# Sensor.net
KiCad netlist of a schematic drawn in Altium Designer
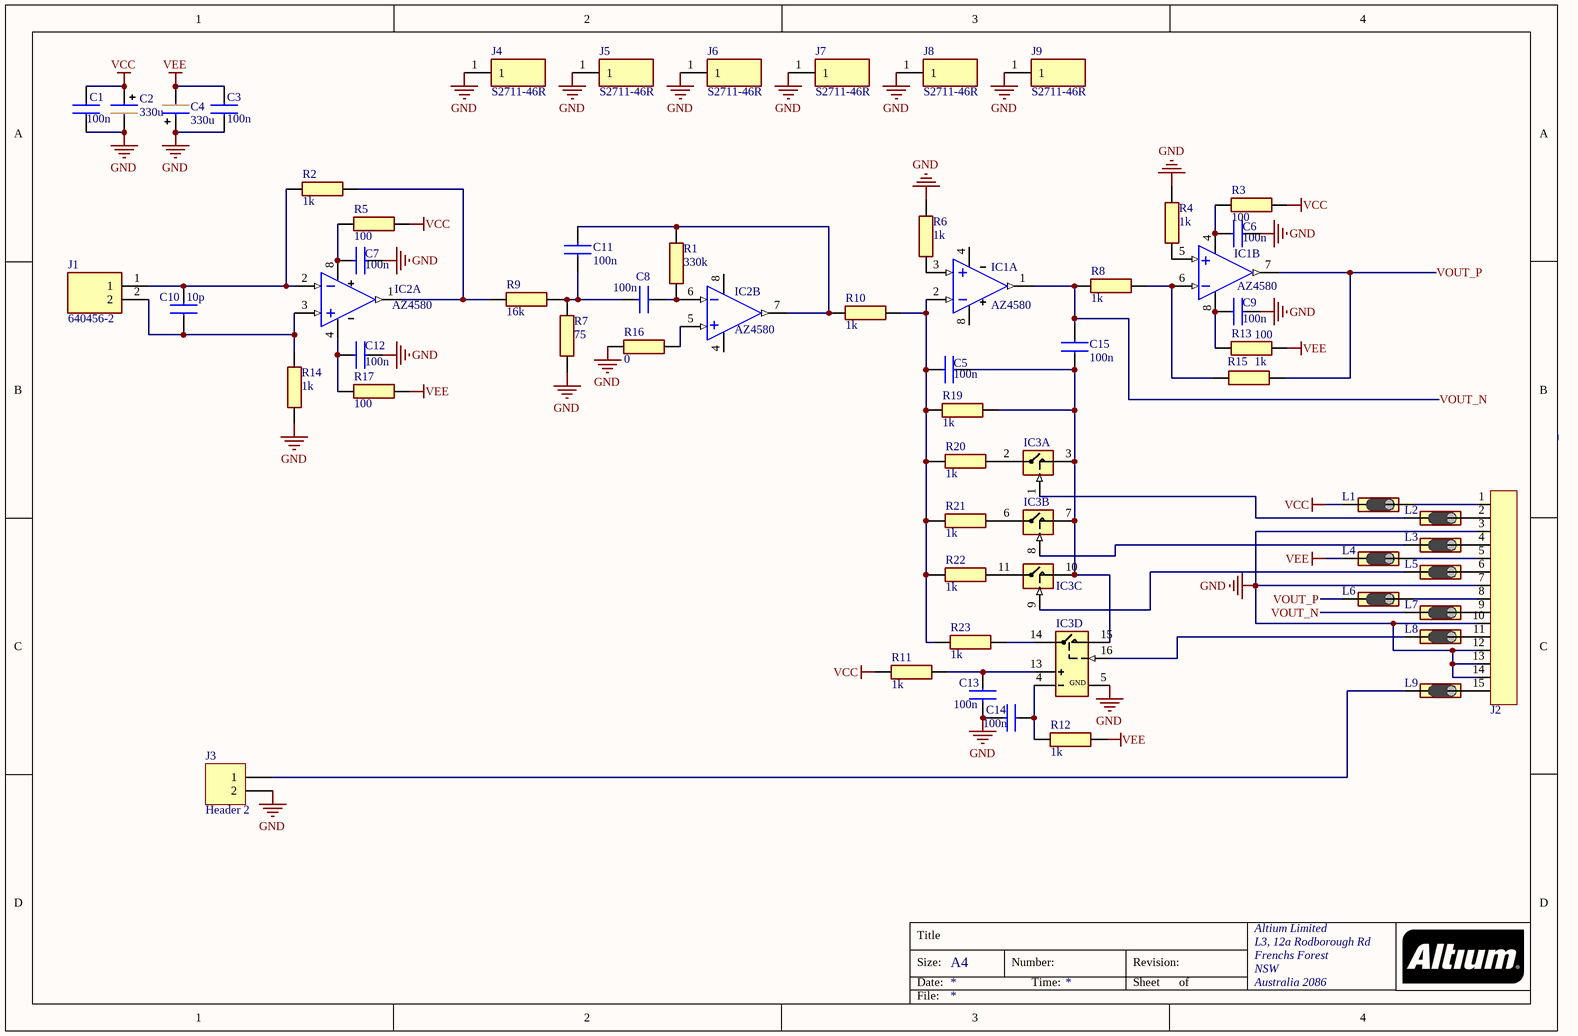
[diagram p0: Sensor.SchDoc]

(export (version "E")
  (design (tool "Eeschema 10.0.6"))
  (components
    (comp (ref "C1")
      (value "100n")
      (footprint "CAPC2012X140N")
      (description "Capacitor smd ceramic")
      (fields
        (field (name "MANUFACTURER_PART_NUMBER") "C3216C0G1H562J060AA")
        (field (name "Comment") "Capacitor_SMD")
      )
      (libsource (lib "Schlib") (part "Capacitor_SMD"))
    )
    (comp (ref "C2")
      (value "330u")
      (footprint "CAP_EL_8X12R3_5")
      (description "Capacitor polarized electrolytic")
      (fields
        (field (name "MANUFACTURER_PART_NUMBER") "B43640A9477M")
        (field (name "MOUSER PART NUMBER") "871-B43640A9477M")
      )
      (libsource (lib "Schlib") (part "Capacitor Electrolytic"))
    )
    (comp (ref "C3")
      (value "100n")
      (footprint "CAPC2012X140N")
      (description "Capacitor smd ceramic")
      (fields
        (field (name "MANUFACTURER_PART_NUMBER") "C3216C0G1H562J060AA")
        (field (name "Comment") "Capacitor_SMD")
      )
      (libsource (lib "Schlib") (part "Capacitor_SMD"))
    )
    (comp (ref "C4")
      (value "330u")
      (footprint "CAP_EL_8X12R3_5")
      (description "Capacitor polarized electrolytic")
      (fields
        (field (name "MANUFACTURER_PART_NUMBER") "B43640A9477M")
        (field (name "MOUSER PART NUMBER") "871-B43640A9477M")
      )
      (libsource (lib "Schlib") (part "Capacitor Electrolytic"))
    )
    (comp (ref "C5")
      (value "100n")
      (footprint "CAPC2012X140N")
      (description "Capacitor smd ceramic")
      (fields
        (field (name "MANUFACTURER_PART_NUMBER") "C3216C0G1H562J060AA")
        (field (name "Comment") "Capacitor_SMD")
      )
      (libsource (lib "Schlib") (part "Capacitor_SMD"))
    )
    (comp (ref "C6")
      (value "100n")
      (footprint "CAPC2012X140N")
      (description "Capacitor smd ceramic")
      (fields
        (field (name "MANUFACTURER_PART_NUMBER") "C3216C0G1H562J060AA")
        (field (name "Comment") "Capacitor_SMD")
      )
      (libsource (lib "Schlib") (part "Capacitor_SMD"))
    )
    (comp (ref "C7")
      (value "100n")
      (footprint "CAPC2012X140N")
      (description "Capacitor smd ceramic")
      (fields
        (field (name "MANUFACTURER_PART_NUMBER") "C3216C0G1H562J060AA")
        (field (name "Comment") "Capacitor_SMD")
      )
      (libsource (lib "Schlib") (part "Capacitor_SMD"))
    )
    (comp (ref "C8")
      (value "100n")
      (footprint "CAPC3216X95N")
      (description "Capacitor smd ceramic")
      (fields
        (field (name "MANUFACTURER_PART_NUMBER") "C3216C0G1H562J060AA")
        (field (name "Comment") "Capacitor_SMD")
      )
      (libsource (lib "Schlib") (part "Capacitor_SMD"))
    )
    (comp (ref "C9")
      (value "100n")
      (footprint "CAPC2012X140N")
      (description "Capacitor smd ceramic")
      (fields
        (field (name "MANUFACTURER_PART_NUMBER") "C3216C0G1H562J060AA")
        (field (name "Comment") "Capacitor_SMD")
      )
      (libsource (lib "Schlib") (part "Capacitor_SMD"))
    )
    (comp (ref "C10")
      (value "10p")
      (footprint "CAPC2012X140N")
      (description "Capacitor smd ceramic")
      (fields
        (field (name "MANUFACTURER_PART_NUMBER") "C3216C0G1H562J060AA")
        (field (name "Comment") "Capacitor_SMD")
      )
      (libsource (lib "Schlib") (part "Capacitor_SMD"))
    )
    (comp (ref "C11")
      (value "100n")
      (footprint "CAPC3216X95N")
      (description "Capacitor smd ceramic")
      (fields
        (field (name "MANUFACTURER_PART_NUMBER") "C3216C0G1H562J060AA")
        (field (name "Comment") "Capacitor_SMD")
      )
      (libsource (lib "Schlib") (part "Capacitor_SMD"))
    )
    (comp (ref "C12")
      (value "100n")
      (footprint "CAPC2012X140N")
      (description "Capacitor smd ceramic")
      (fields
        (field (name "MANUFACTURER_PART_NUMBER") "C3216C0G1H562J060AA")
        (field (name "Comment") "Capacitor_SMD")
      )
      (libsource (lib "Schlib") (part "Capacitor_SMD"))
    )
    (comp (ref "C13")
      (value "100n")
      (footprint "CAPC2012X140N")
      (description "Capacitor smd ceramic")
      (fields
        (field (name "MANUFACTURER_PART_NUMBER") "C3216C0G1H562J060AA")
        (field (name "Comment") "Capacitor_SMD")
      )
      (libsource (lib "Schlib") (part "Capacitor_SMD"))
    )
    (comp (ref "C14")
      (value "100n")
      (footprint "CAPC2012X140N")
      (description "Capacitor smd ceramic")
      (fields
        (field (name "MANUFACTURER_PART_NUMBER") "C3216C0G1H562J060AA")
        (field (name "Comment") "Capacitor_SMD")
      )
      (libsource (lib "Schlib") (part "Capacitor_SMD"))
    )
    (comp (ref "C15")
      (value "100n")
      (footprint "CAPC3216X95N")
      (description "Capacitor smd ceramic")
      (fields
        (field (name "MANUFACTURER_PART_NUMBER") "C3216C0G1H562J060AA")
        (field (name "Comment") "Capacitor_SMD")
      )
      (libsource (lib "Schlib") (part "Capacitor_SMD"))
    )
    (comp (ref "IC1")
      (value "AZ4580")
      (footprint "SOP65P490X110-8N")
      (description "Operational amplifier")
      (fields (field (name "ARROW PART NUMBER") "AZ4580"))
      (libsource (lib "Schlib") (part "AZ4580"))
    )
    (comp (ref "IC2")
      (value "AZ4580")
      (footprint "SOP65P490X110-8N")
      (description "Operational amplifier")
      (fields (field (name "ARROW PART NUMBER") "AZ4580"))
      (libsource (lib "Schlib") (part "AZ4580"))
    )
    (comp (ref "IC3")
      (value "DG442DY-E3")
      (footprint "PcbLib:SOIC127P600X175-16N")
      (description "Integrated Circuit")
      (fields (field (name "MOUSER PART NUMBER") "781-DG442DY-E3"))
      (libsource (lib "Schlib") (part "DG442DY-E3"))
    )
    (comp (ref "J1")
      (value "640456-2")
      (footprint "PcbLib:SHDR2W66P0X254_1X2_508X572X1041P")
      (description "Connector")
      (fields (field (name "MOUSER PART NUMBER") "571-6404562"))
      (libsource (lib "Schlib") (part "640456-2"))
    )
    (comp (ref "J2")
      (value "D-Sub 15 pin")
      (footprint "PcbLib:ICD15S13E4GV00LF")
      (description "Connector D sub 9 pin pcb angled 90")
      (fields
        (field (name "MANUFACTURER_PART_NUMBER") "ICD15S13E4GV00LF")
        (field (name "MOUSER PART NUMBER") "649-ICD15S13E4GV00LF")
      )
      (libsource (lib "Schlib") (part "D-Sub 15 pin"))
    )
    (comp (ref "J3")
      (value "Header 2")
      (footprint "HDR1X2")
      (description "Header, 2-Pin")
      (fields (field (name "PUBLISHER") "Altium Limited"))
      (libsource (lib "Miscellaneous Connectors") (part "Header 2"))
    )
    (comp (ref "J4")
      (value "S2711-46R")
      (footprint "PcbLib:S271146R")
      (description "Connector")
      (fields (field (name "MOUSER PART NUMBER") "855-S2711-46R"))
      (libsource (lib "Schlib") (part "S2711-46R"))
    )
    (comp (ref "J5")
      (value "S2711-46R")
      (footprint "PcbLib:S271146R")
      (description "Connector")
      (fields (field (name "MOUSER PART NUMBER") "855-S2711-46R"))
      (libsource (lib "Schlib") (part "S2711-46R"))
    )
    (comp (ref "J6")
      (value "S2711-46R")
      (footprint "PcbLib:S271146R")
      (description "Connector")
      (fields (field (name "MOUSER PART NUMBER") "855-S2711-46R"))
      (libsource (lib "Schlib") (part "S2711-46R"))
    )
    (comp (ref "J7")
      (value "S2711-46R")
      (footprint "PcbLib:S271146R")
      (description "Connector")
      (fields (field (name "MOUSER PART NUMBER") "855-S2711-46R"))
      (libsource (lib "Schlib") (part "S2711-46R"))
    )
    (comp (ref "J8")
      (value "S2711-46R")
      (footprint "PcbLib:S271146R")
      (description "Connector")
      (fields (field (name "MOUSER PART NUMBER") "855-S2711-46R"))
      (libsource (lib "Schlib") (part "S2711-46R"))
    )
    (comp (ref "J9")
      (value "S2711-46R")
      (footprint "PcbLib:S271146R")
      (description "Connector")
      (fields (field (name "MOUSER PART NUMBER") "855-S2711-46R"))
      (libsource (lib "Schlib") (part "S2711-46R"))
    )
    (comp (ref "L1")
      (value "Ferrite Bead")
      (footprint "RESC2012X60N")
      (description "Bead ferrite")
      (libsource (lib "Schlib") (part "Ferrite Bead"))
    )
    (comp (ref "L2")
      (value "Ferrite Bead")
      (footprint "RESC2012X60N")
      (description "Bead ferrite")
      (libsource (lib "Schlib") (part "Ferrite Bead"))
    )
    (comp (ref "L3")
      (value "Ferrite Bead")
      (footprint "RESC2012X60N")
      (description "Bead ferrite")
      (libsource (lib "Schlib") (part "Ferrite Bead"))
    )
    (comp (ref "L4")
      (value "Ferrite Bead")
      (footprint "RESC2012X60N")
      (description "Bead ferrite")
      (libsource (lib "Schlib") (part "Ferrite Bead"))
    )
    (comp (ref "L5")
      (value "Ferrite Bead")
      (footprint "RESC2012X60N")
      (description "Bead ferrite")
      (libsource (lib "Schlib") (part "Ferrite Bead"))
    )
    (comp (ref "L6")
      (value "Ferrite Bead")
      (footprint "RESC2012X60N")
      (description "Bead ferrite")
      (libsource (lib "Schlib") (part "Ferrite Bead"))
    )
    (comp (ref "L7")
      (value "Ferrite Bead")
      (footprint "RESC2012X60N")
      (description "Bead ferrite")
      (libsource (lib "Schlib") (part "Ferrite Bead"))
    )
    (comp (ref "L8")
      (value "Ferrite Bead")
      (footprint "RESC2012X60N")
      (description "Bead ferrite")
      (libsource (lib "Schlib") (part "Ferrite Bead"))
    )
    (comp (ref "L9")
      (value "Ferrite Bead")
      (footprint "RESC2012X60N")
      (description "Bead ferrite")
      (libsource (lib "Schlib") (part "Ferrite Bead"))
    )
    (comp (ref "R1")
      (value "330k")
      (footprint "RESC2012X60N")
      (description "Resistor SMD")
      (fields
        (field (name "MANUFACTURER_PART_NUMBER") "CR1206-FW-1504ELF")
        (field (name "MOUSER PART NUMBER") "652-CR1206FW1504ELF")
      )
      (libsource (lib "Schlib") (part "Res_SMD"))
    )
    (comp (ref "R2")
      (value "1k")
      (footprint "RESC2012X60N")
      (description "Resistor SMD")
      (fields
        (field (name "MANUFACTURER_PART_NUMBER") "CR1206-FW-1504ELF")
        (field (name "MOUSER PART NUMBER") "652-CR1206FW1504ELF")
      )
      (libsource (lib "") (part "Res_SMD_2"))
    )
    (comp (ref "R3")
      (value "100")
      (footprint "RESC2012X60N")
      (description "Resistor SMD")
      (fields
        (field (name "MANUFACTURER_PART_NUMBER") "CR1206-FW-1504ELF")
        (field (name "MOUSER PART NUMBER") "652-CR1206FW1504ELF")
      )
      (libsource (lib "") (part "Res_SMD_1"))
    )
    (comp (ref "R4")
      (value "1k")
      (footprint "RESC2012X60N")
      (description "Resistor SMD")
      (fields
        (field (name "MANUFACTURER_PART_NUMBER") "CR1206-FW-1504ELF")
        (field (name "MOUSER PART NUMBER") "652-CR1206FW1504ELF")
      )
      (libsource (lib "") (part "Res_SMD_1"))
    )
    (comp (ref "R5")
      (value "100")
      (footprint "RESC2012X60N")
      (description "Resistor SMD")
      (fields
        (field (name "MANUFACTURER_PART_NUMBER") "CR1206-FW-1504ELF")
        (field (name "MOUSER PART NUMBER") "652-CR1206FW1504ELF")
      )
      (libsource (lib "") (part "Res_SMD_1"))
    )
    (comp (ref "R6")
      (value "1k")
      (footprint "RESC2012X60N")
      (description "Resistor SMD")
      (fields
        (field (name "MANUFACTURER_PART_NUMBER") "CR1206-FW-1504ELF")
        (field (name "MOUSER PART NUMBER") "652-CR1206FW1504ELF")
      )
      (libsource (lib "") (part "Res_SMD_1"))
    )
    (comp (ref "R7")
      (value "75")
      (footprint "RESC2012X60N")
      (description "Resistor SMD")
      (fields
        (field (name "MANUFACTURER_PART_NUMBER") "CR1206-FW-1504ELF")
        (field (name "MOUSER PART NUMBER") "652-CR1206FW1504ELF")
      )
      (libsource (lib "Schlib") (part "Res_SMD"))
    )
    (comp (ref "R8")
      (value "1k")
      (footprint "RESC2012X60N")
      (description "Resistor SMD")
      (fields
        (field (name "MANUFACTURER_PART_NUMBER") "CR1206-FW-1504ELF")
        (field (name "MOUSER PART NUMBER") "652-CR1206FW1504ELF")
      )
      (libsource (lib "") (part "Res_SMD_1"))
    )
    (comp (ref "R9")
      (value "16k")
      (footprint "RESC2012X60N")
      (description "Resistor SMD")
      (fields
        (field (name "MANUFACTURER_PART_NUMBER") "CR1206-FW-1504ELF")
        (field (name "MOUSER PART NUMBER") "652-CR1206FW1504ELF")
      )
      (libsource (lib "") (part "Res_SMD_2"))
    )
    (comp (ref "R10")
      (value "1k")
      (footprint "RESC2012X60N")
      (description "Resistor SMD")
      (fields
        (field (name "MANUFACTURER_PART_NUMBER") "CR1206-FW-1504ELF")
        (field (name "MOUSER PART NUMBER") "652-CR1206FW1504ELF")
      )
      (libsource (lib "") (part "Res_SMD_2"))
    )
    (comp (ref "R11")
      (value "1k")
      (footprint "RESC2012X60N")
      (description "Resistor SMD")
      (fields
        (field (name "MANUFACTURER_PART_NUMBER") "CR1206-FW-1504ELF")
        (field (name "MOUSER PART NUMBER") "652-CR1206FW1504ELF")
      )
      (libsource (lib "Schlib") (part "Res_SMD"))
    )
    (comp (ref "R12")
      (value "1k")
      (footprint "RESC2012X60N")
      (description "Resistor SMD")
      (fields
        (field (name "MANUFACTURER_PART_NUMBER") "CR1206-FW-1504ELF")
        (field (name "MOUSER PART NUMBER") "652-CR1206FW1504ELF")
      )
      (libsource (lib "Schlib") (part "Res_SMD"))
    )
    (comp (ref "R13")
      (value "100")
      (footprint "RESC2012X60N")
      (description "Resistor SMD")
      (fields
        (field (name "MANUFACTURER_PART_NUMBER") "CR1206-FW-1504ELF")
        (field (name "MOUSER PART NUMBER") "652-CR1206FW1504ELF")
      )
      (libsource (lib "") (part "Res_SMD_1"))
    )
    (comp (ref "R14")
      (value "1k")
      (footprint "RESC2012X60N")
      (description "Resistor SMD")
      (fields
        (field (name "MANUFACTURER_PART_NUMBER") "CR1206-FW-1504ELF")
        (field (name "MOUSER PART NUMBER") "652-CR1206FW1504ELF")
      )
      (libsource (lib "Schlib") (part "Res_SMD"))
    )
    (comp (ref "R15")
      (value "1k")
      (footprint "RESC2012X60N")
      (description "Resistor SMD")
      (fields
        (field (name "MANUFACTURER_PART_NUMBER") "CR1206-FW-1504ELF")
        (field (name "MOUSER PART NUMBER") "652-CR1206FW1504ELF")
      )
      (libsource (lib "") (part "Res_SMD_1"))
    )
    (comp (ref "R16")
      (value "0")
      (footprint "RESC2012X60N")
      (description "Resistor SMD")
      (fields
        (field (name "MANUFACTURER_PART_NUMBER") "CR1206-FW-1504ELF")
        (field (name "MOUSER PART NUMBER") "652-CR1206FW1504ELF")
      )
      (libsource (lib "") (part "Res_SMD_2"))
    )
    (comp (ref "R17")
      (value "100")
      (footprint "RESC2012X60N")
      (description "Resistor SMD")
      (fields
        (field (name "MANUFACTURER_PART_NUMBER") "CR1206-FW-1504ELF")
        (field (name "MOUSER PART NUMBER") "652-CR1206FW1504ELF")
      )
      (libsource (lib "") (part "Res_SMD_1"))
    )
    (comp (ref "R19")
      (value "1k")
      (footprint "RESC2012X60N")
      (description "Resistor SMD")
      (fields
        (field (name "MANUFACTURER_PART_NUMBER") "CR1206-FW-1504ELF")
        (field (name "MOUSER PART NUMBER") "652-CR1206FW1504ELF")
      )
      (libsource (lib "") (part "Res_SMD_2"))
    )
    (comp (ref "R20")
      (value "1k")
      (footprint "RESC2012X60N")
      (description "Resistor SMD")
      (fields
        (field (name "MANUFACTURER_PART_NUMBER") "CR1206-FW-1504ELF")
        (field (name "MOUSER PART NUMBER") "652-CR1206FW1504ELF")
      )
      (libsource (lib "Schlib") (part "Res_SMD"))
    )
    (comp (ref "R21")
      (value "1k")
      (footprint "RESC2012X60N")
      (description "Resistor SMD")
      (fields
        (field (name "MANUFACTURER_PART_NUMBER") "CR1206-FW-1504ELF")
        (field (name "MOUSER PART NUMBER") "652-CR1206FW1504ELF")
      )
      (libsource (lib "Schlib") (part "Res_SMD"))
    )
    (comp (ref "R22")
      (value "1k")
      (footprint "RESC2012X60N")
      (description "Resistor SMD")
      (fields
        (field (name "MANUFACTURER_PART_NUMBER") "CR1206-FW-1504ELF")
        (field (name "MOUSER PART NUMBER") "652-CR1206FW1504ELF")
      )
      (libsource (lib "Schlib") (part "Res_SMD"))
    )
    (comp (ref "R23")
      (value "1k")
      (footprint "RESC2012X60N")
      (description "Resistor SMD")
      (fields
        (field (name "MANUFACTURER_PART_NUMBER") "CR1206-FW-1504ELF")
        (field (name "MOUSER PART NUMBER") "652-CR1206FW1504ELF")
      )
      (libsource (lib "Schlib") (part "Res_SMD"))
    )
  )
  (nets
    (net (code "1") (name "/VOUT_N") (class "Default")
      (node (ref "C15") (pin "1") (pinfunction "1_1") (pintype "passive"))
      (node (ref "IC1") (pin "1") (pinfunction "OUT_1") (pintype "output"))
      (node (ref "L7") (pin "1") (pinfunction "1_1") (pintype "passive"))
      (node (ref "R8") (pin "2") (pinfunction "2_2") (pintype "passive"))
    )
    (net (code "2") (name "/VOUT_P") (class "Default")
      (node (ref "IC1") (pin "7") (pinfunction "OUT_7") (pintype "output"))
      (node (ref "L6") (pin "1") (pinfunction "1_1") (pintype "passive"))
      (node (ref "R15") (pin "1") (pinfunction "1_1") (pintype "passive"))
    )
    (net (code "3") (name "GND") (class "Default")
      (node (ref "C1") (pin "2") (pinfunction "2_2") (pintype "passive"))
      (node (ref "C12") (pin "1") (pinfunction "1_1") (pintype "passive"))
      (node (ref "C13") (pin "2") (pinfunction "2_2") (pintype "passive"))
      (node (ref "C14") (pin "1") (pinfunction "1_1") (pintype "passive"))
      (node (ref "C2") (pin "2") (pinfunction "-_2") (pintype "passive"))
      (node (ref "C3") (pin "2") (pinfunction "2_2") (pintype "passive"))
      (node (ref "C4") (pin "1") (pinfunction "+_1") (pintype "passive"))
      (node (ref "C6") (pin "1") (pinfunction "1_1") (pintype "passive"))
      (node (ref "C7") (pin "1") (pinfunction "1_1") (pintype "passive"))
      (node (ref "C9") (pin "1") (pinfunction "1_1") (pintype "passive"))
      (node (ref "IC3") (pin "5") (pinfunction "GND_5") (pintype "power_in"))
      (node (ref "J2") (pin "10") (pintype "passive"))
      (node (ref "J2") (pin "12") (pintype "passive"))
      (node (ref "J2") (pin "13") (pintype "passive"))
      (node (ref "J2") (pin "14") (pintype "passive"))
      (node (ref "J2") (pin "3") (pintype "passive"))
      (node (ref "J2") (pin "7") (pintype "passive"))
      (node (ref "J3") (pin "2") (pinfunction "2_2") (pintype "passive"))
      (node (ref "J4") (pin "1") (pinfunction "1_1") (pintype "passive"))
      (node (ref "J5") (pin "1") (pinfunction "1_1") (pintype "passive"))
      (node (ref "J6") (pin "1") (pinfunction "1_1") (pintype "passive"))
      (node (ref "J7") (pin "1") (pinfunction "1_1") (pintype "passive"))
      (node (ref "J8") (pin "1") (pinfunction "1_1") (pintype "passive"))
      (node (ref "J9") (pin "1") (pinfunction "1_1") (pintype "passive"))
      (node (ref "R14") (pin "1") (pinfunction "1_1") (pintype "passive"))
      (node (ref "R16") (pin "1") (pinfunction "1_1") (pintype "passive"))
      (node (ref "R4") (pin "1") (pinfunction "1_1") (pintype "passive"))
      (node (ref "R6") (pin "1") (pinfunction "1_1") (pintype "passive"))
      (node (ref "R7") (pin "1") (pinfunction "1_1") (pintype "passive"))
    )
    (net (code "4") (name "Net-(C11-Pad1)") (class "Default")
      (node (ref "C11") (pin "1") (pinfunction "1_1") (pintype "passive"))
      (node (ref "C8") (pin "1") (pinfunction "1_1") (pintype "passive"))
      (node (ref "R7") (pin "2") (pinfunction "2_2") (pintype "passive"))
      (node (ref "R9") (pin "2") (pinfunction "2_2") (pintype "passive"))
    )
    (net (code "5") (name "Net-(IC1A-IN+)") (class "Default")
      (node (ref "IC1") (pin "3") (pinfunction "IN+_3") (pintype "input"))
      (node (ref "R6") (pin "2") (pinfunction "2_2") (pintype "passive"))
    )
    (net (code "6") (name "Net-(IC1A-IN-)") (class "Default")
      (node (ref "C5") (pin "2") (pinfunction "2_2") (pintype "passive"))
      (node (ref "IC1") (pin "2") (pinfunction "IN-_2") (pintype "input"))
      (node (ref "R10") (pin "2") (pinfunction "2_2") (pintype "passive"))
      (node (ref "R19") (pin "1") (pinfunction "1_1") (pintype "passive"))
      (node (ref "R20") (pin "1") (pinfunction "1_1") (pintype "passive"))
      (node (ref "R21") (pin "1") (pinfunction "1_1") (pintype "passive"))
      (node (ref "R22") (pin "1") (pinfunction "1_1") (pintype "passive"))
      (node (ref "R23") (pin "1") (pinfunction "1_1") (pintype "passive"))
    )
    (net (code "7") (name "Net-(IC1B-IN+)") (class "Default")
      (node (ref "IC1") (pin "5") (pinfunction "IN+_5") (pintype "input"))
      (node (ref "R4") (pin "2") (pinfunction "2_2") (pintype "passive"))
    )
    (net (code "8") (name "Net-(IC1B-IN-)") (class "Default")
      (node (ref "IC1") (pin "6") (pinfunction "IN-_6") (pintype "input"))
      (node (ref "R15") (pin "2") (pinfunction "2_2") (pintype "passive"))
      (node (ref "R8") (pin "1") (pinfunction "1_1") (pintype "passive"))
    )
    (net (code "9") (name "Net-(IC1B-V+)") (class "Default")
      (node (ref "C9") (pin "2") (pinfunction "2_2") (pintype "passive"))
      (node (ref "IC1") (pin "8") (pinfunction "V+_8") (pintype "power_in"))
      (node (ref "R13") (pin "2") (pinfunction "2_2") (pintype "passive"))
    )
    (net (code "10") (name "Net-(IC1B-V-)") (class "Default")
      (node (ref "C6") (pin "2") (pinfunction "2_2") (pintype "passive"))
      (node (ref "IC1") (pin "4") (pinfunction "V-_4") (pintype "power_in"))
      (node (ref "R3") (pin "2") (pinfunction "2_2") (pintype "passive"))
    )
    (net (code "11") (name "Net-(IC2A-IN+)") (class "Default")
      (node (ref "C10") (pin "2") (pinfunction "2_2") (pintype "passive"))
      (node (ref "IC2") (pin "3") (pinfunction "IN+_3") (pintype "input"))
      (node (ref "J1") (pin "2") (pinfunction "2_2") (pintype "passive"))
      (node (ref "R14") (pin "2") (pinfunction "2_2") (pintype "passive"))
    )
    (net (code "12") (name "Net-(IC2A-IN-)") (class "Default")
      (node (ref "C10") (pin "1") (pinfunction "1_1") (pintype "passive"))
      (node (ref "IC2") (pin "2") (pinfunction "IN-_2") (pintype "input"))
      (node (ref "J1") (pin "1") (pinfunction "1_1") (pintype "passive"))
      (node (ref "R2") (pin "1") (pinfunction "1_1") (pintype "passive"))
    )
    (net (code "13") (name "Net-(IC2A-OUT)") (class "Default")
      (node (ref "IC2") (pin "1") (pinfunction "OUT_1") (pintype "output"))
      (node (ref "R2") (pin "2") (pinfunction "2_2") (pintype "passive"))
      (node (ref "R9") (pin "1") (pinfunction "1_1") (pintype "passive"))
    )
    (net (code "14") (name "Net-(IC2A-V+)") (class "Default")
      (node (ref "C7") (pin "2") (pinfunction "2_2") (pintype "passive"))
      (node (ref "IC2") (pin "8") (pinfunction "V+_8") (pintype "power_in"))
      (node (ref "R5") (pin "2") (pinfunction "2_2") (pintype "passive"))
    )
    (net (code "15") (name "Net-(IC2A-V-)") (class "Default")
      (node (ref "C12") (pin "2") (pinfunction "2_2") (pintype "passive"))
      (node (ref "IC2") (pin "4") (pinfunction "V-_4") (pintype "power_in"))
      (node (ref "R17") (pin "2") (pinfunction "2_2") (pintype "passive"))
    )
    (net (code "16") (name "Net-(IC2B-IN+)") (class "Default")
      (node (ref "IC2") (pin "5") (pinfunction "IN+_5") (pintype "input"))
      (node (ref "R16") (pin "2") (pinfunction "2_2") (pintype "passive"))
    )
    (net (code "17") (name "Net-(IC2B-IN-)") (class "Default")
      (node (ref "C8") (pin "2") (pinfunction "2_2") (pintype "passive"))
      (node (ref "IC2") (pin "6") (pinfunction "IN-_6") (pintype "input"))
      (node (ref "R1") (pin "1") (pinfunction "1_1") (pintype "passive"))
    )
    (net (code "18") (name "Net-(IC2B-OUT)") (class "Default")
      (node (ref "C11") (pin "2") (pinfunction "2_2") (pintype "passive"))
      (node (ref "IC2") (pin "7") (pinfunction "OUT_7") (pintype "output"))
      (node (ref "R1") (pin "2") (pinfunction "2_2") (pintype "passive"))
      (node (ref "R10") (pin "1") (pinfunction "1_1") (pintype "passive"))
    )
    (net (code "19") (name "Net-(IC3A-D1)") (class "Default")
      (node (ref "IC3") (pin "2") (pinfunction "D1_2") (pintype "passive"))
      (node (ref "R20") (pin "2") (pinfunction "2_2") (pintype "passive"))
    )
    (net (code "20") (name "Net-(IC3A-IN1)") (class "Default")
      (node (ref "IC3") (pin "1") (pinfunction "IN1_1") (pintype "input"))
      (node (ref "L2") (pin "1") (pinfunction "1_1") (pintype "passive"))
    )
    (net (code "21") (name "Net-(IC3A-S1)") (class "Default")
      (node (ref "C15") (pin "2") (pinfunction "2_2") (pintype "passive"))
      (node (ref "C5") (pin "1") (pinfunction "1_1") (pintype "passive"))
      (node (ref "IC3") (pin "10") (pinfunction "D3_10") (pintype "passive"))
      (node (ref "IC3") (pin "15") (pinfunction "D2_15") (pintype "passive"))
      (node (ref "IC3") (pin "3") (pinfunction "S1_3") (pintype "passive"))
      (node (ref "IC3") (pin "7") (pinfunction "D4_7") (pintype "passive"))
      (node (ref "R19") (pin "2") (pinfunction "2_2") (pintype "passive"))
    )
    (net (code "22") (name "Net-(IC3B-IN4)") (class "Default")
      (node (ref "IC3") (pin "8") (pinfunction "IN4_8") (pintype "input"))
      (node (ref "L3") (pin "1") (pinfunction "1_1") (pintype "passive"))
    )
    (net (code "23") (name "Net-(IC3B-S4)") (class "Default")
      (node (ref "IC3") (pin "6") (pinfunction "S4_6") (pintype "passive"))
      (node (ref "R21") (pin "2") (pinfunction "2_2") (pintype "passive"))
    )
    (net (code "24") (name "Net-(IC3C-IN3)") (class "Default")
      (node (ref "IC3") (pin "9") (pinfunction "IN3_9") (pintype "input"))
      (node (ref "L5") (pin "1") (pinfunction "1_1") (pintype "passive"))
    )
    (net (code "25") (name "Net-(IC3C-S3)") (class "Default")
      (node (ref "IC3") (pin "11") (pinfunction "S3_11") (pintype "passive"))
      (node (ref "R22") (pin "2") (pinfunction "2_2") (pintype "passive"))
    )
    (net (code "26") (name "Net-(IC3D-IN2)") (class "Default")
      (node (ref "IC3") (pin "16") (pinfunction "IN2_16") (pintype "input"))
      (node (ref "L8") (pin "1") (pinfunction "1_1") (pintype "passive"))
    )
    (net (code "27") (name "Net-(IC3D-S2)") (class "Default")
      (node (ref "IC3") (pin "14") (pinfunction "S2_14") (pintype "passive"))
      (node (ref "R23") (pin "2") (pinfunction "2_2") (pintype "passive"))
    )
    (net (code "28") (name "Net-(IC3D-V+)") (class "Default")
      (node (ref "C13") (pin "1") (pinfunction "1_1") (pintype "passive"))
      (node (ref "IC3") (pin "13") (pinfunction "V+_13") (pintype "power_in"))
      (node (ref "R11") (pin "2") (pinfunction "2_2") (pintype "passive"))
    )
    (net (code "29") (name "Net-(IC3D-V-)") (class "Default")
      (node (ref "C14") (pin "2") (pinfunction "2_2") (pintype "passive"))
      (node (ref "IC3") (pin "4") (pinfunction "V-_4") (pintype "power_in"))
      (node (ref "R12") (pin "1") (pinfunction "1_1") (pintype "passive"))
    )
    (net (code "30") (name "Net-(J2-Pad1)") (class "Default")
      (node (ref "J2") (pin "1") (pintype "passive"))
      (node (ref "L1") (pin "2") (pinfunction "2_2") (pintype "passive"))
    )
    (net (code "31") (name "Net-(J2-Pad2)") (class "Default")
      (node (ref "J2") (pin "2") (pintype "passive"))
      (node (ref "L2") (pin "2") (pinfunction "2_2") (pintype "passive"))
    )
    (net (code "32") (name "Net-(J2-Pad4)") (class "Default")
      (node (ref "J2") (pin "4") (pintype "passive"))
      (node (ref "L3") (pin "2") (pinfunction "2_2") (pintype "passive"))
    )
    (net (code "33") (name "Net-(J2-Pad5)") (class "Default")
      (node (ref "J2") (pin "5") (pintype "passive"))
      (node (ref "L4") (pin "2") (pinfunction "2_2") (pintype "passive"))
    )
    (net (code "34") (name "Net-(J2-Pad6)") (class "Default")
      (node (ref "J2") (pin "6") (pintype "passive"))
      (node (ref "L5") (pin "2") (pinfunction "2_2") (pintype "passive"))
    )
    (net (code "35") (name "Net-(J2-Pad8)") (class "Default")
      (node (ref "J2") (pin "8") (pintype "passive"))
      (node (ref "L6") (pin "2") (pinfunction "2_2") (pintype "passive"))
    )
    (net (code "36") (name "Net-(J2-Pad9)") (class "Default")
      (node (ref "J2") (pin "9") (pintype "passive"))
      (node (ref "L7") (pin "2") (pinfunction "2_2") (pintype "passive"))
    )
    (net (code "37") (name "Net-(J2-Pad11)") (class "Default")
      (node (ref "J2") (pin "11") (pintype "passive"))
      (node (ref "L8") (pin "2") (pinfunction "2_2") (pintype "passive"))
    )
    (net (code "38") (name "Net-(J2-Pad15)") (class "Default")
      (node (ref "J2") (pin "15") (pintype "passive"))
      (node (ref "L9") (pin "2") (pinfunction "2_2") (pintype "passive"))
    )
    (net (code "39") (name "Net-(J3-Pad1)") (class "Default")
      (node (ref "J3") (pin "1") (pinfunction "1_1") (pintype "passive"))
      (node (ref "L9") (pin "1") (pinfunction "1_1") (pintype "passive"))
    )
    (net (code "40") (name "VCC") (class "Default")
      (node (ref "C1") (pin "1") (pinfunction "1_1") (pintype "passive"))
      (node (ref "C2") (pin "1") (pinfunction "+_1") (pintype "passive"))
      (node (ref "L1") (pin "1") (pinfunction "1_1") (pintype "passive"))
      (node (ref "R11") (pin "1") (pinfunction "1_1") (pintype "passive"))
      (node (ref "R3") (pin "1") (pinfunction "1_1") (pintype "passive"))
      (node (ref "R5") (pin "1") (pinfunction "1_1") (pintype "passive"))
    )
    (net (code "41") (name "VEE") (class "Default")
      (node (ref "C3") (pin "1") (pinfunction "1_1") (pintype "passive"))
      (node (ref "C4") (pin "2") (pinfunction "-_2") (pintype "passive"))
      (node (ref "L4") (pin "1") (pinfunction "1_1") (pintype "passive"))
      (node (ref "R12") (pin "2") (pinfunction "2_2") (pintype "passive"))
      (node (ref "R13") (pin "1") (pinfunction "1_1") (pintype "passive"))
      (node (ref "R17") (pin "1") (pinfunction "1_1") (pintype "passive"))
    )
    (net (code "42") (name "unconnected-(IC1A-V+-Pad8)") (class "Default")
      (node (ref "IC1") (pin "8") (pinfunction "V+_8") (pintype "power_in"))
    )
    (net (code "43") (name "unconnected-(IC1A-V--Pad4)") (class "Default")
      (node (ref "IC1") (pin "4") (pinfunction "V-_4") (pintype "power_in"))
    )
    (net (code "44") (name "unconnected-(IC2B-V+-Pad8)") (class "Default")
      (node (ref "IC2") (pin "8") (pinfunction "V+_8") (pintype "power_in"))
    )
    (net (code "45") (name "unconnected-(IC2B-V--Pad4)") (class "Default")
      (node (ref "IC2") (pin "4") (pinfunction "V-_4") (pintype "power_in"))
    )
  )
)
